# Connectors.net
KiCad netlist of a schematic drawn in Altium Designer
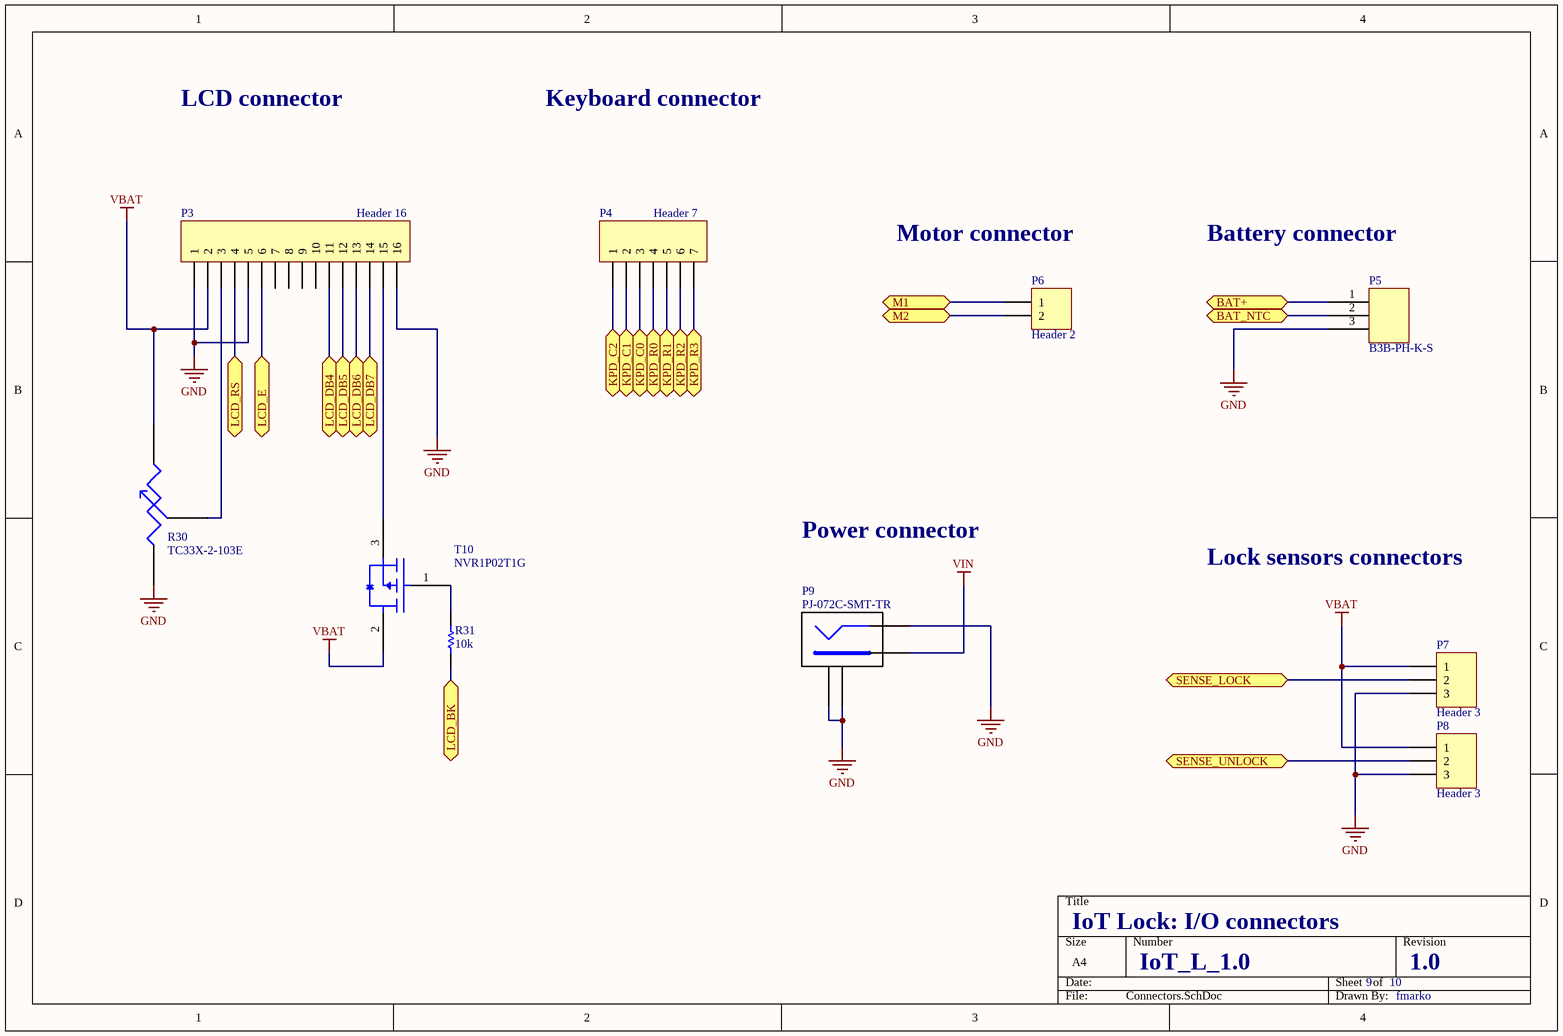
[diagram p0: Connectors.SchDoc]

(export (version "E")
  (design (tool "Eeschema 10.0.6"))
  (components
    (comp (ref "P3")
      (value "Header 16")
      (footprint "HDR1X16")
      (description "Header, 16-Pin")
      (fields (field (name "PUBLISHER") "Altium Limited"))
      (libsource (lib "Miscellaneous Connectors") (part "Header 16"))
    )
    (comp (ref "P4")
      (value "Header 7")
      (footprint "HDR1X7")
      (description "Header, 7-Pin")
      (fields (field (name "PUBLISHER") "Altium Limited"))
      (libsource (lib "Miscellaneous Connectors") (part "Header 7"))
    )
    (comp (ref "P5")
      (value "B3B-PH-K-S")
      (footprint "B3B-PH-K-S")
      (description "JST connector, 3-pin, 2mm pitch")
      (libsource (lib "B3B-PH-K-S") (part "B3B-PH-K-S"))
    )
    (comp (ref "P6")
      (value "Header 2")
      (footprint "HDR1X2")
      (description "Header, 2-Pin")
      (fields (field (name "PUBLISHER") "Altium Limited"))
      (libsource (lib "Miscellaneous Connectors") (part "Header 2"))
    )
    (comp (ref "P7")
      (value "Header 3")
      (footprint "HDR1X3")
      (description "Header, 3-Pin")
      (fields (field (name "PUBLISHER") "Altium Limited"))
      (libsource (lib "Miscellaneous Connectors") (part "Header 3"))
    )
    (comp (ref "P8")
      (value "Header 3")
      (footprint "HDR1X3")
      (description "Header, 3-Pin")
      (fields (field (name "PUBLISHER") "Altium Limited"))
      (libsource (lib "Miscellaneous Connectors") (part "Header 3"))
    )
    (comp (ref "P9")
      (value "PJ-072C-SMT-TR")
      (footprint "PJ-072C-SMT-TR_HOUSING")
      (description "CUI Barrel power connector, 1X3.4mm")
      (libsource (lib "PJ-072C-SMT-TR") (part "PJ-072C-SMT-TR"))
    )
    (comp (ref "R30")
      (value "TC33X-2-103E")
      (footprint "TC33X-2-XXX_HOUSING")
      (description "SMD trimmer resistor, 10k")
      (libsource (lib "TC33X-2-103E") (part "TC33X-2-103E"))
    )
    (comp (ref "R31")
      (value "10k")
      (footprint "0402")
      (description "Semiconductor Resistor")
      (fields (field (name "Comment") "Res Semi") (field (name "PUBLISHER") "Altium Limited"))
      (libsource (lib "Miscellaneous Devices") (part "Res Semi"))
    )
    (comp (ref "T10")
      (value "NVR1P02T1G")
      (footprint "SOT95P237X111-3N")
      (description "P-Channel MOSFET")
      (libsource (lib "NVR1P02T1G") (part "NVR1P02T1G"))
    )
  )
  (nets
    (net (code "1") (name "/BAT+") (class "Default") (node (ref "P5") (pin "1") (pintype "passive")))
    (net (code "2") (name "/BAT_NTC") (class "Default") (node (ref "P5") (pin "2") (pintype "passive")))
    (net (code "3") (name "/KPD_C0") (class "Default")
      (node (ref "P4") (pin "3") (pinfunction "3_3") (pintype "passive"))
    )
    (net (code "4") (name "/KPD_C1") (class "Default")
      (node (ref "P4") (pin "2") (pinfunction "2_2") (pintype "passive"))
    )
    (net (code "5") (name "/KPD_C2") (class "Default")
      (node (ref "P4") (pin "1") (pinfunction "1_1") (pintype "passive"))
    )
    (net (code "6") (name "/KPD_R0") (class "Default")
      (node (ref "P4") (pin "4") (pinfunction "4_4") (pintype "passive"))
    )
    (net (code "7") (name "/KPD_R1") (class "Default")
      (node (ref "P4") (pin "5") (pinfunction "5_5") (pintype "passive"))
    )
    (net (code "8") (name "/KPD_R2") (class "Default")
      (node (ref "P4") (pin "6") (pinfunction "6_6") (pintype "passive"))
    )
    (net (code "9") (name "/KPD_R3") (class "Default")
      (node (ref "P4") (pin "7") (pinfunction "7_7") (pintype "passive"))
    )
    (net (code "10") (name "/LCD_BK") (class "Default")
      (node (ref "R31") (pin "1") (pinfunction "1_1") (pintype "passive"))
    )
    (net (code "11") (name "/LCD_DB4") (class "Default")
      (node (ref "P3") (pin "11") (pinfunction "11_11") (pintype "passive"))
    )
    (net (code "12") (name "/LCD_DB5") (class "Default")
      (node (ref "P3") (pin "12") (pinfunction "12_12") (pintype "passive"))
    )
    (net (code "13") (name "/LCD_DB6") (class "Default")
      (node (ref "P3") (pin "13") (pinfunction "13_13") (pintype "passive"))
    )
    (net (code "14") (name "/LCD_DB7") (class "Default")
      (node (ref "P3") (pin "14") (pinfunction "14_14") (pintype "passive"))
    )
    (net (code "15") (name "/LCD_E") (class "Default")
      (node (ref "P3") (pin "6") (pinfunction "6_6") (pintype "passive"))
    )
    (net (code "16") (name "/LCD_RS") (class "Default")
      (node (ref "P3") (pin "4") (pinfunction "4_4") (pintype "passive"))
    )
    (net (code "17") (name "/M1") (class "Default")
      (node (ref "P6") (pin "1") (pinfunction "1_1") (pintype "passive"))
    )
    (net (code "18") (name "/M2") (class "Default")
      (node (ref "P6") (pin "2") (pinfunction "2_2") (pintype "passive"))
    )
    (net (code "19") (name "/SENSE_LOCK") (class "Default")
      (node (ref "P7") (pin "2") (pinfunction "2_2") (pintype "passive"))
    )
    (net (code "20") (name "/SENSE_UNLOCK") (class "Default")
      (node (ref "P8") (pin "2") (pinfunction "2_2") (pintype "passive"))
    )
    (net (code "21") (name "GND") (class "Default")
      (node (ref "P3") (pin "1") (pinfunction "1_1") (pintype "passive"))
      (node (ref "P3") (pin "16") (pinfunction "16_16") (pintype "passive"))
      (node (ref "P3") (pin "5") (pinfunction "5_5") (pintype "passive"))
      (node (ref "P5") (pin "3") (pintype "passive"))
      (node (ref "P7") (pin "3") (pinfunction "3_3") (pintype "passive"))
      (node (ref "P8") (pin "3") (pinfunction "3_3") (pintype "passive"))
      (node (ref "P9") (pin "2") (pinfunction "GND_2") (pintype "passive"))
      (node (ref "P9") (pin "3") (pinfunction "SHD_3") (pintype "passive"))
      (node (ref "P9") (pin "4") (pinfunction "SHD_4") (pintype "passive"))
      (node (ref "R30") (pin "1") (pintype "passive"))
    )
    (net (code "22") (name "Net-(P3-Pad3)") (class "Default")
      (node (ref "P3") (pin "3") (pinfunction "3_3") (pintype "passive"))
      (node (ref "R30") (pin "2") (pintype "passive"))
    )
    (net (code "23") (name "Net-(T10-D)") (class "Default")
      (node (ref "P3") (pin "15") (pinfunction "15_15") (pintype "passive"))
      (node (ref "T10") (pin "3") (pinfunction "D_3") (pintype "passive"))
    )
    (net (code "24") (name "Net-(T10-G)") (class "Default")
      (node (ref "R31") (pin "2") (pinfunction "2_2") (pintype "passive"))
      (node (ref "T10") (pin "1") (pinfunction "G_1") (pintype "passive"))
    )
    (net (code "25") (name "VBAT") (class "Default")
      (node (ref "P3") (pin "2") (pinfunction "2_2") (pintype "passive"))
      (node (ref "P7") (pin "1") (pinfunction "1_1") (pintype "passive"))
      (node (ref "P8") (pin "1") (pinfunction "1_1") (pintype "passive"))
      (node (ref "R30") (pin "3") (pintype "passive"))
      (node (ref "T10") (pin "2") (pinfunction "S_2") (pintype "passive"))
    )
    (net (code "26") (name "VIN") (class "Default")
      (node (ref "P9") (pin "1") (pinfunction "PWR_1") (pintype "passive"))
    )
    (net (code "27") (name "unconnected-(P3-Pad7)") (class "Default")
      (node (ref "P3") (pin "7") (pinfunction "7_7") (pintype "passive"))
    )
    (net (code "28") (name "unconnected-(P3-Pad8)") (class "Default")
      (node (ref "P3") (pin "8") (pinfunction "8_8") (pintype "passive"))
    )
    (net (code "29") (name "unconnected-(P3-Pad9)") (class "Default")
      (node (ref "P3") (pin "9") (pinfunction "9_9") (pintype "passive"))
    )
    (net (code "30") (name "unconnected-(P3-Pad10)") (class "Default")
      (node (ref "P3") (pin "10") (pinfunction "10_10") (pintype "passive"))
    )
  )
)
